# Quad_FC_V10_1.net
KiCad netlist of a schematic drawn in Altium Designer
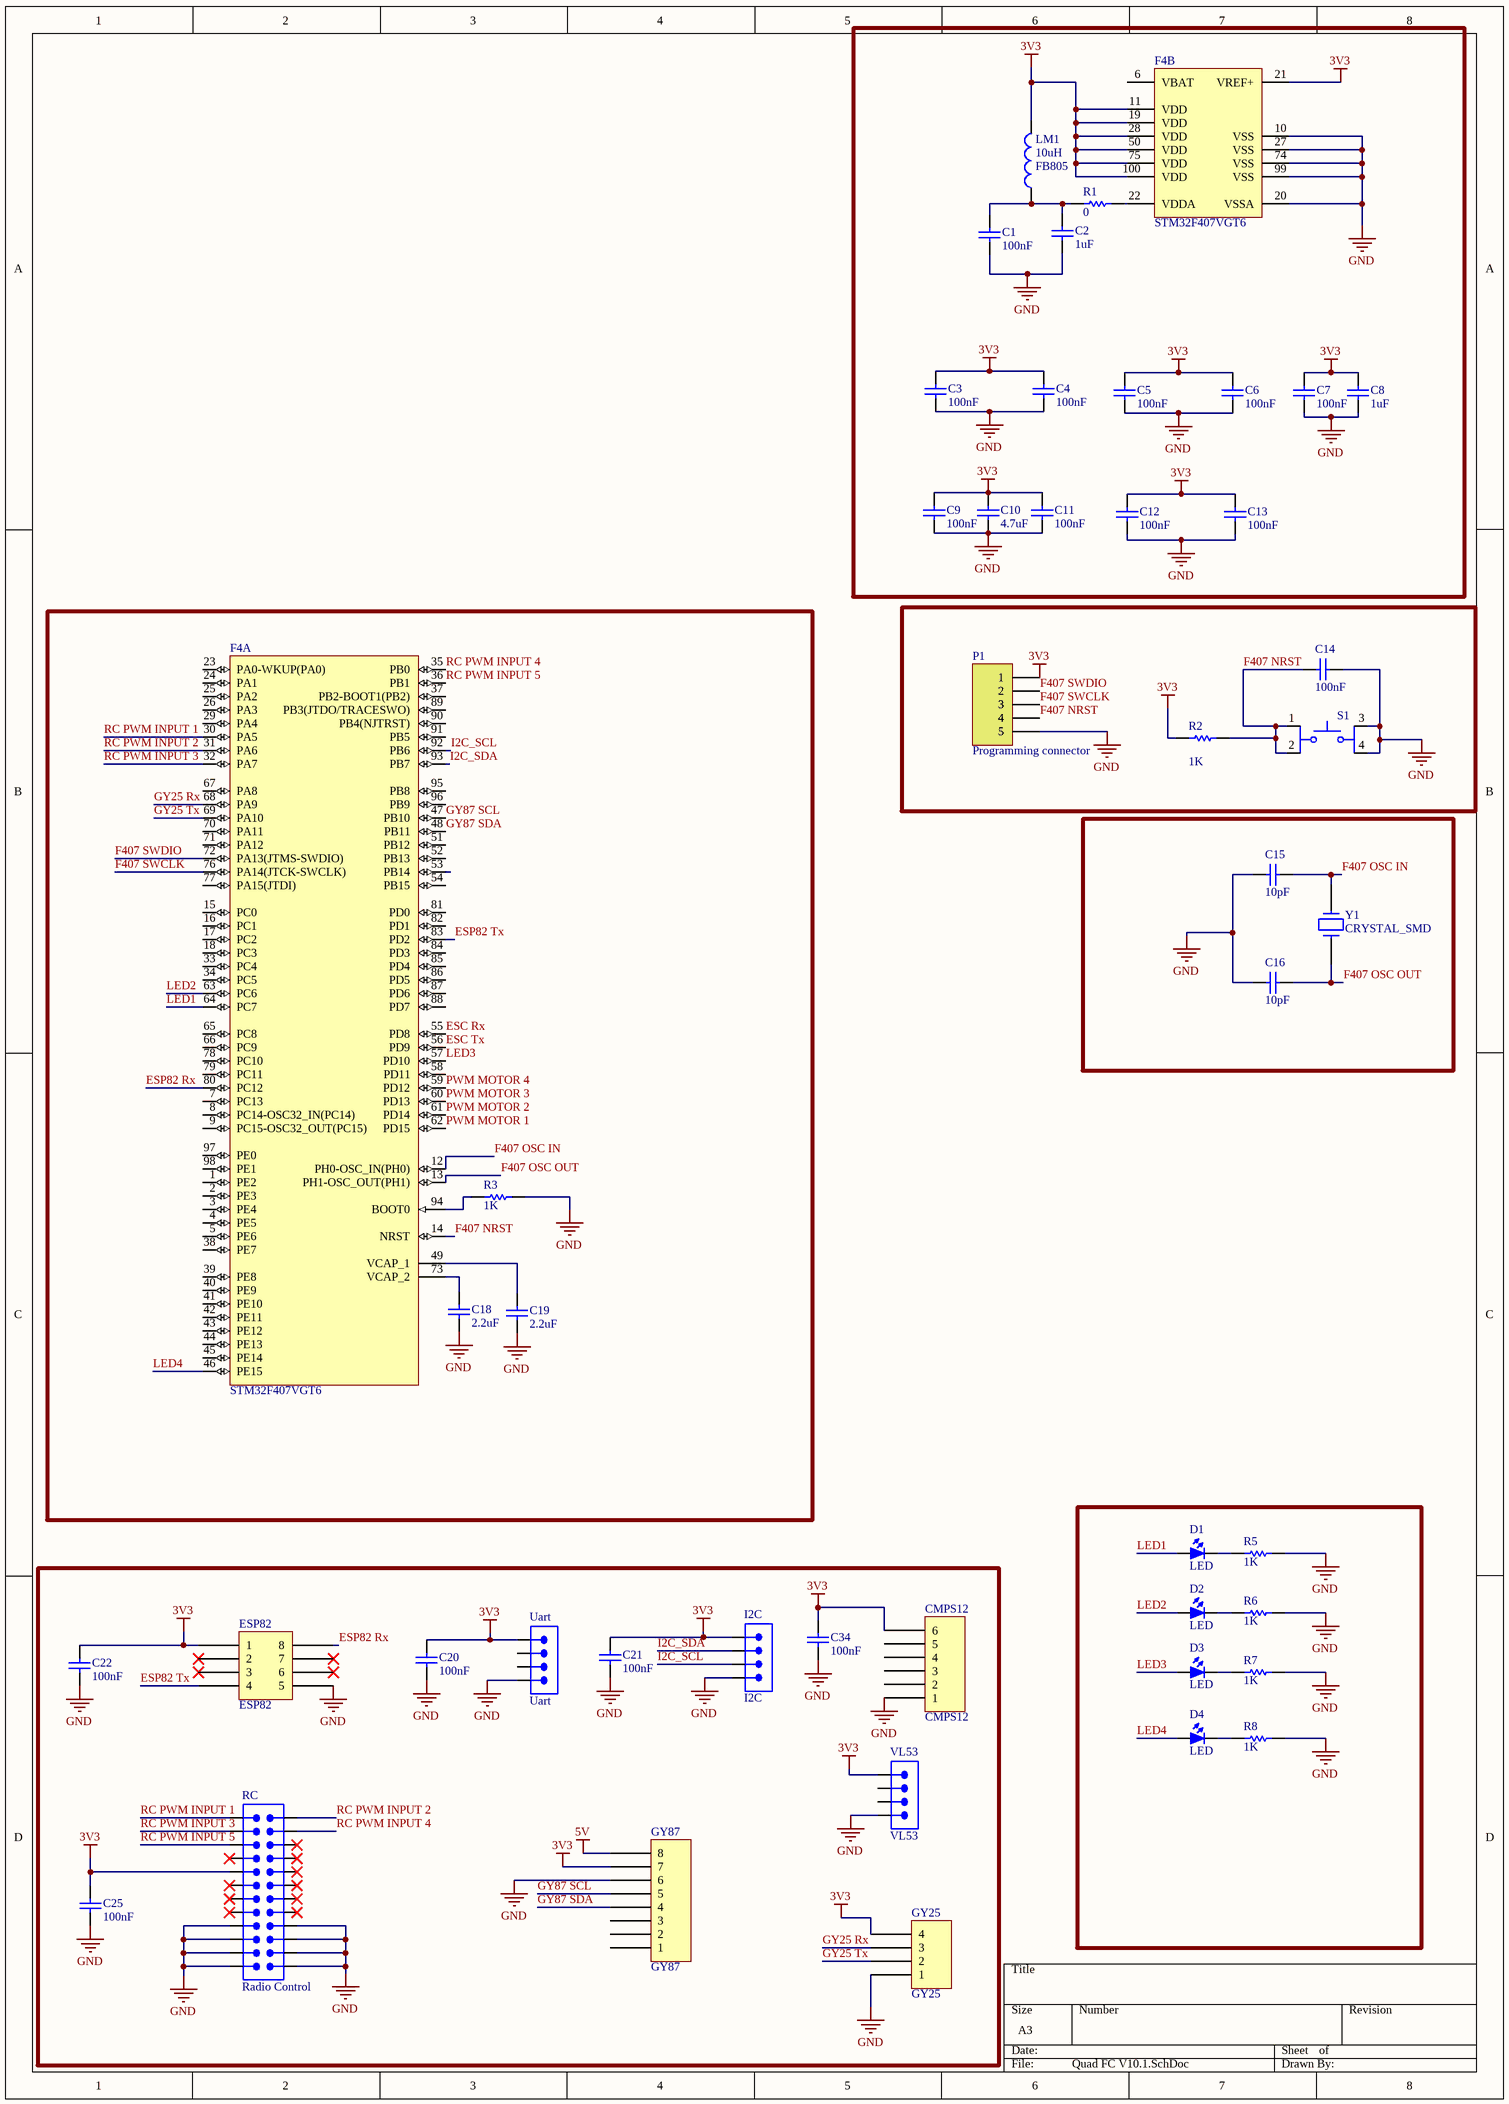
[diagram p0: Quad FC V10.1.SchDoc]

(export (version "E")
  (design (tool "Eeschema 10.0.6"))
  (components
    (comp (ref "C1")
      (value "100nF")
      (footprint "CAP0603")
      (description "F407VET6 Power CAP")
      (fields (field (name "DESIGNER") "Abbas Basereh"))
      (libsource (lib "2017AbbasBasereh9365731239 -ver1") (part "CAP SMD PACKAGE"))
    )
    (comp (ref "C2")
      (value "1uF")
      (footprint "CAP0603")
      (description "F407VET6 Power CAP")
      (fields (field (name "DESIGNER") "Abbas Basereh"))
      (libsource (lib "2017AbbasBasereh9365731239 -ver1") (part "CAP SMD PACKAGE"))
    )
    (comp (ref "C3")
      (value "100nF")
      (footprint "CAP0603")
      (description "F407VET6 Power CAP")
      (fields (field (name "DESIGNER") "Abbas Basereh"))
      (libsource (lib "2017AbbasBasereh9365731239 -ver1") (part "CAP SMD PACKAGE"))
    )
    (comp (ref "C4")
      (value "100nF")
      (footprint "CAP0603")
      (description "F407VET6 Power CAP")
      (fields (field (name "DESIGNER") "Abbas Basereh"))
      (libsource (lib "2017AbbasBasereh9365731239 -ver1") (part "CAP SMD PACKAGE"))
    )
    (comp (ref "C5")
      (value "100nF")
      (footprint "CAP0603")
      (description "F407VET6 Power CAP")
      (fields (field (name "DESIGNER") "Abbas Basereh"))
      (libsource (lib "2017AbbasBasereh9365731239 -ver1") (part "CAP SMD PACKAGE"))
    )
    (comp (ref "C6")
      (value "100nF")
      (footprint "CAP0603")
      (description "F407VET6 Power CAP")
      (fields (field (name "DESIGNER") "Abbas Basereh"))
      (libsource (lib "2017AbbasBasereh9365731239 -ver1") (part "CAP SMD PACKAGE"))
    )
    (comp (ref "C7")
      (value "100nF")
      (footprint "CAP0603")
      (description "F407VET6 Power CAP")
      (fields (field (name "DESIGNER") "Abbas Basereh"))
      (libsource (lib "2017AbbasBasereh9365731239 -ver1") (part "CAP SMD PACKAGE"))
    )
    (comp (ref "C8")
      (value "1uF")
      (footprint "CAP0603")
      (description "F407VET6 Power CAP")
      (fields (field (name "DESIGNER") "Abbas Basereh"))
      (libsource (lib "2017AbbasBasereh9365731239 -ver1") (part "CAP SMD PACKAGE"))
    )
    (comp (ref "C9")
      (value "100nF")
      (footprint "CAP0603")
      (description "F407VET6 Power CAP")
      (fields (field (name "DESIGNER") "Abbas Basereh"))
      (libsource (lib "2017AbbasBasereh9365731239 -ver1") (part "CAP SMD PACKAGE"))
    )
    (comp (ref "C10")
      (value "4.7uF")
      (footprint "CAP0603")
      (description "F407VET6 Power CAP")
      (fields (field (name "DESIGNER") "Abbas Basereh"))
      (libsource (lib "2017AbbasBasereh9365731239 -ver1") (part "CAP SMD PACKAGE"))
    )
    (comp (ref "C11")
      (value "100nF")
      (footprint "CAP0603")
      (description "F407VET6 Power CAP")
      (fields (field (name "DESIGNER") "Abbas Basereh"))
      (libsource (lib "2017AbbasBasereh9365731239 -ver1") (part "CAP SMD PACKAGE"))
    )
    (comp (ref "C12")
      (value "100nF")
      (footprint "CAP0603")
      (description "F407VET6 Power CAP")
      (fields (field (name "DESIGNER") "Abbas Basereh"))
      (libsource (lib "2017AbbasBasereh9365731239 -ver1") (part "CAP SMD PACKAGE"))
    )
    (comp (ref "C13")
      (value "100nF")
      (footprint "CAP0603")
      (description "F407VET6 Power CAP")
      (fields (field (name "DESIGNER") "Abbas Basereh"))
      (libsource (lib "2017AbbasBasereh9365731239 -ver1") (part "CAP SMD PACKAGE"))
    )
    (comp (ref "C14")
      (value "100nF")
      (footprint "CAP0603")
      (description "F407VET6 Power CAP")
      (fields (field (name "DESIGNER") "Abbas Basereh"))
      (libsource (lib "2017AbbasBasereh9365731239 -ver1") (part "CAP SMD PACKAGE"))
    )
    (comp (ref "C15")
      (value "10pF")
      (footprint "CAP0603")
      (description "F407VET6 Power CAP")
      (fields (field (name "DESIGNER") "Abbas Basereh"))
      (libsource (lib "2017AbbasBasereh9365731239 -ver1") (part "CAP SMD PACKAGE"))
    )
    (comp (ref "C16")
      (value "10pF")
      (footprint "CAP0603")
      (description "F407VET6 Power CAP")
      (fields (field (name "DESIGNER") "Abbas Basereh"))
      (libsource (lib "2017AbbasBasereh9365731239 -ver1") (part "CAP SMD PACKAGE"))
    )
    (comp (ref "C18")
      (value "2.2uF")
      (footprint "CAP0603")
      (description "F407VET6 Power CAP")
      (fields (field (name "DESIGNER") "Abbas Basereh"))
      (libsource (lib "2017AbbasBasereh9365731239 -ver1") (part "CAP SMD PACKAGE"))
    )
    (comp (ref "C19")
      (value "2.2uF")
      (footprint "CAP0603")
      (description "F407VET6 Power CAP")
      (fields (field (name "DESIGNER") "Abbas Basereh"))
      (libsource (lib "2017AbbasBasereh9365731239 -ver1") (part "CAP SMD PACKAGE"))
    )
    (comp (ref "C20")
      (value "100nF")
      (footprint "CAP0603")
      (description "F407VET6 Power CAP")
      (fields (field (name "DESIGNER") "Abbas Basereh"))
      (libsource (lib "2017AbbasBasereh9365731239 -ver1") (part "CAP SMD PACKAGE"))
    )
    (comp (ref "C21")
      (value "100nF")
      (footprint "CAP0603")
      (description "F407VET6 Power CAP")
      (fields (field (name "DESIGNER") "Abbas Basereh"))
      (libsource (lib "2017AbbasBasereh9365731239 -ver1") (part "CAP SMD PACKAGE"))
    )
    (comp (ref "C22")
      (value "100nF")
      (footprint "CAP0603")
      (description "F407VET6 Power CAP")
      (fields (field (name "DESIGNER") "Abbas Basereh"))
      (libsource (lib "2017AbbasBasereh9365731239 -ver1") (part "CAP SMD PACKAGE"))
    )
    (comp (ref "C25")
      (value "100nF")
      (footprint "CAP0603")
      (description "F407VET6 Power CAP")
      (fields (field (name "DESIGNER") "Abbas Basereh"))
      (libsource (lib "2017AbbasBasereh9365731239 -ver1") (part "CAP SMD PACKAGE"))
    )
    (comp (ref "C34")
      (value "100nF")
      (footprint "CAP0603")
      (description "F407VET6 Power CAP")
      (fields (field (name "DESIGNER") "Abbas Basereh"))
      (libsource (lib "2017AbbasBasereh9365731239 -ver1") (part "CAP SMD PACKAGE"))
    )
    (comp (ref "CMPS12")
      (value "CMPS12")
      (footprint "SAMTEC SSW-106-03-T-S")
      (description "CONN RCPT 6POS 0.1 TIN PCB")
      (fields (field (name "PART NUMBER") "SSW-106-03-T-S") (field (name "MANUFACTURER") "Samtec Inc."))
      (libsource (lib "Celestial Altium Library - altium_library (1)") (part "6 Pin"))
    )
    (comp (ref "D1")
      (value "LED")
      (footprint "0603 - LED")
      (description "Led")
      (fields (field (name "PUBLISHER") "Altium Limited"))
      (libsource (lib "Sajad_Altium_Library") (part "LED"))
    )
    (comp (ref "D2")
      (value "LED")
      (footprint "0603 - LED")
      (description "Led")
      (fields (field (name "PUBLISHER") "Altium Limited"))
      (libsource (lib "Sajad_Altium_Library") (part "LED"))
    )
    (comp (ref "D3")
      (value "LED")
      (footprint "0603 - LED")
      (description "Led")
      (fields (field (name "PUBLISHER") "Altium Limited"))
      (libsource (lib "Sajad_Altium_Library") (part "LED"))
    )
    (comp (ref "D4")
      (value "LED")
      (footprint "0603 - LED")
      (description "Led")
      (fields (field (name "PUBLISHER") "Altium Limited"))
      (libsource (lib "Sajad_Altium_Library") (part "LED"))
    )
    (comp (ref "ESP82")
      (value "ESP82")
      (footprint "HARWIN M20-7830445")
      (description "CONN RCPT 8POS 0.1 GOLD PCB")
      (fields (field (name "PART NUMBER") "M20-7830442") (field (name "MANUFACTURER") "Harwin Inc."))
      (libsource (lib "Celestial Altium Library - altium_library (1)") (part "2X4 PIN DU"))
    )
    (comp (ref "F4")
      (value "STM32F407VGT6")
      (footprint "STM-LQFP100_N")
      (fields (field (name "MANUFACTURER") "STMicroelectronics"))
      (libsource (lib "STMicroelectronics STM32 F4") (part "STM32F407VGT6"))
    )
    (comp (ref "GY25")
      (value "GY25")
      (footprint "SAMTEC SSW-104-03-T-S")
      (description "CONN RCPT 4POS 0.1 TIN PCB")
      (fields (field (name "PART NUMBER") "SSW-104-03-T-S") (field (name "MANUFACTURER") "Samtec Inc."))
      (libsource (lib "Celestial Altium Library - altium_library (1)") (part "4 Pin"))
    )
    (comp (ref "GY87")
      (value "GY87")
      (footprint "SAMTEC SSW-108-03-T-S")
      (description "CONN RCPT 8POS 0.1 TIN PCB")
      (fields (field (name "PART NUMBER") "SSW-108-03-T-S") (field (name "MANUFACTURER") "Samtec Inc."))
      (libsource (lib "Celestial Altium Library - altium_library (1)") (part "8 Pin"))
    )
    (comp (ref "I2C")
      (value "I2C")
      (footprint "JST BM04B-SURS-TF")
      (description "Male Header 1X04")
      (libsource (lib "SJ Sockets & Connectors") (part "MHDR_1X04"))
    )
    (comp (ref "LM1")
      (value "10uH")
      (footprint "0805L")
      (description "Inductor")
      (fields (field (name "ALTIUM_VALUE") "FB805") (field (name "PUBLISHER") "Altium Limited"))
      (libsource (lib "2017AbbasBasereh9365731239 -ver1") (part "L SMA 0.25W"))
    )
    (comp (ref "P1")
      (value "Programming connector")
      (footprint "Connector1X5")
      (description "Connector, 5-Pin2.5mm")
      (fields (field (name "PUBLISHER") "Altium Limited"))
      (libsource (lib "Sajad_Altium_Library") (part "Connector1x5"))
    )
    (comp (ref "R1")
      (value "0")
      (footprint "RES0603")
      (description "TOTAL SMD RESISTOR PACK")
      (fields (field (name "DESIGNER") "Abbas Basereh"))
      (libsource (lib "2017AbbasBasereh9365731239 -ver1") (part "RES SMD PACKAGE"))
    )
    (comp (ref "R2")
      (value "1K")
      (footprint "RES0603")
      (description "TOTAL SMD RESISTOR PACK")
      (fields (field (name "DESIGNER") "Abbas Basereh"))
      (libsource (lib "2017AbbasBasereh9365731239 -ver1") (part "RES SMD PACKAGE"))
    )
    (comp (ref "R3")
      (value "1K")
      (footprint "RES0603")
      (description "TOTAL SMD RESISTOR PACK")
      (fields (field (name "DESIGNER") "Abbas Basereh"))
      (libsource (lib "2017AbbasBasereh9365731239 -ver1") (part "RES SMD PACKAGE"))
    )
    (comp (ref "R5")
      (value "1K")
      (footprint "RES0603")
      (description "TOTAL SMD RESISTOR PACK")
      (fields (field (name "DESIGNER") "Abbas Basereh"))
      (libsource (lib "2017AbbasBasereh9365731239 -ver1") (part "RES SMD PACKAGE"))
    )
    (comp (ref "R6")
      (value "1K")
      (footprint "RES0603")
      (description "TOTAL SMD RESISTOR PACK")
      (fields (field (name "DESIGNER") "Abbas Basereh"))
      (libsource (lib "2017AbbasBasereh9365731239 -ver1") (part "RES SMD PACKAGE"))
    )
    (comp (ref "R7")
      (value "1K")
      (footprint "RES0603")
      (description "TOTAL SMD RESISTOR PACK")
      (fields (field (name "DESIGNER") "Abbas Basereh"))
      (libsource (lib "2017AbbasBasereh9365731239 -ver1") (part "RES SMD PACKAGE"))
    )
    (comp (ref "R8")
      (value "1K")
      (footprint "RES0603")
      (description "TOTAL SMD RESISTOR PACK")
      (fields (field (name "DESIGNER") "Abbas Basereh"))
      (libsource (lib "2017AbbasBasereh9365731239 -ver1") (part "RES SMD PACKAGE"))
    )
    (comp (ref "RC")
      (value "Radio Control")
      (footprint "HEADER8X3:HEADER8X3")
      (description "Male Header 2X12")
      (libsource (lib "SJ Sockets & Connectors") (part "MHDR_2X12"))
    )
    (comp (ref "S1")
      (value "~")
      (footprint "SW_TL3301FF160QG")
      (description "Tactile switch for manual RESET")
      (fields (field (name "MF") "E-Switch") (field (name "MP") "TL3301FF160QG"))
      (libsource (lib "Tactile switch 6x6") (part "TL3301FF160QG"))
    )
    (comp (ref "Uart")
      (value "Uart")
      (footprint "JST BM04B-SURS-TF")
      (description "Male Header 1X04")
      (libsource (lib "SJ Sockets & Connectors") (part "MHDR_1X04"))
    )
    (comp (ref "VL53")
      (value "VL53")
      (footprint "JST BM04B-SURS-TF")
      (description "Male Header 1X04")
      (libsource (lib "SJ Sockets & Connectors") (part "MHDR_1X04"))
    )
    (comp (ref "Y1")
      (value "CRYSTAL_SMD")
      (footprint "My_Crystal - SMD")
      (description "Crystal")
      (libsource (lib "AMINLIB") (part "CRYSTAL_SMD"))
    )
  )
  (nets
    (net (code "1") (name "/ESC Rx") (class "Default")
      (node (ref "F4") (pin "55") (pinfunction "PD8_55") (pintype "bidirectional"))
    )
    (net (code "2") (name "/ESC Tx") (class "Default")
      (node (ref "F4") (pin "56") (pinfunction "PD9_56") (pintype "bidirectional"))
    )
    (net (code "3") (name "/ESP82 Rx") (class "Default")
      (node (ref "ESP82") (pin "8") (pinfunction "8_8") (pintype "passive"))
      (node (ref "F4") (pin "80") (pinfunction "PC12_80") (pintype "bidirectional"))
    )
    (net (code "4") (name "/ESP82 Tx") (class "Default")
      (node (ref "ESP82") (pin "4") (pinfunction "4_4") (pintype "passive"))
      (node (ref "F4") (pin "83") (pinfunction "PD2_83") (pintype "bidirectional"))
    )
    (net (code "5") (name "/F407 NRST") (class "Default")
      (node (ref "C14") (pin "1") (pinfunction "1_1") (pintype "passive"))
      (node (ref "F4") (pin "14") (pinfunction "NRST_14") (pintype "bidirectional"))
      (node (ref "P1") (pin "4") (pinfunction "4_4") (pintype "passive"))
      (node (ref "R2") (pin "2") (pinfunction "2_2") (pintype "passive"))
      (node (ref "S1") (pin "1") (pinfunction "1_1") (pintype "passive"))
      (node (ref "S1") (pin "2") (pinfunction "2_2") (pintype "passive"))
    )
    (net (code "6") (name "/F407 OSC IN") (class "Default")
      (node (ref "C15") (pin "2") (pinfunction "2_2") (pintype "passive"))
      (node (ref "F4") (pin "12") (pinfunction "PH0-OSC_IN(PH0)_12") (pintype "bidirectional"))
      (node (ref "Y1") (pin "2") (pinfunction "2_2") (pintype "passive"))
    )
    (net (code "7") (name "/F407 OSC OUT") (class "Default")
      (node (ref "C16") (pin "1") (pinfunction "1_1") (pintype "passive"))
      (node (ref "F4") (pin "13") (pinfunction "PH1-OSC_OUT(PH1)_13") (pintype "bidirectional"))
      (node (ref "Y1") (pin "1") (pinfunction "1_1") (pintype "passive"))
    )
    (net (code "8") (name "/F407 SWCLK") (class "Default")
      (node (ref "F4") (pin "76") (pinfunction "PA14(JTCK-SWCLK)_76") (pintype "bidirectional"))
      (node (ref "P1") (pin "3") (pinfunction "3_3") (pintype "passive"))
    )
    (net (code "9") (name "/F407 SWDIO") (class "Default")
      (node (ref "F4") (pin "72") (pinfunction "PA13(JTMS-SWDIO)_72") (pintype "bidirectional"))
      (node (ref "P1") (pin "2") (pinfunction "2_2") (pintype "passive"))
    )
    (net (code "10") (name "/GY25 Rx") (class "Default")
      (node (ref "F4") (pin "68") (pinfunction "PA9_68") (pintype "bidirectional"))
      (node (ref "GY25") (pin "3") (pinfunction "3_3") (pintype "passive"))
    )
    (net (code "11") (name "/GY25 Tx") (class "Default")
      (node (ref "F4") (pin "69") (pinfunction "PA10_69") (pintype "bidirectional"))
      (node (ref "GY25") (pin "2") (pinfunction "2_2") (pintype "passive"))
    )
    (net (code "12") (name "/GY87 SCL") (class "Default")
      (node (ref "F4") (pin "47") (pinfunction "PB10_47") (pintype "bidirectional"))
      (node (ref "GY87") (pin "5") (pinfunction "5_5") (pintype "passive"))
    )
    (net (code "13") (name "/GY87 SDA") (class "Default")
      (node (ref "F4") (pin "48") (pinfunction "PB11_48") (pintype "bidirectional"))
      (node (ref "GY87") (pin "4") (pinfunction "4_4") (pintype "passive"))
    )
    (net (code "14") (name "/I2C_SCL") (class "Default")
      (node (ref "F4") (pin "92") (pinfunction "PB6_92") (pintype "bidirectional"))
      (node (ref "I2C") (pin "3") (pinfunction "3_3") (pintype "passive"))
    )
    (net (code "15") (name "/I2C_SDA") (class "Default")
      (node (ref "F4") (pin "93") (pinfunction "PB7_93") (pintype "bidirectional"))
      (node (ref "I2C") (pin "2") (pinfunction "2_2") (pintype "passive"))
    )
    (net (code "16") (name "/LED1") (class "Default")
      (node (ref "D1") (pin "1") (pinfunction "A_1") (pintype "passive"))
      (node (ref "F4") (pin "64") (pinfunction "PC7_64") (pintype "bidirectional"))
    )
    (net (code "17") (name "/LED2") (class "Default")
      (node (ref "D2") (pin "1") (pinfunction "A_1") (pintype "passive"))
      (node (ref "F4") (pin "63") (pinfunction "PC6_63") (pintype "bidirectional"))
    )
    (net (code "18") (name "/LED3") (class "Default")
      (node (ref "D3") (pin "1") (pinfunction "A_1") (pintype "passive"))
      (node (ref "F4") (pin "57") (pinfunction "PD10_57") (pintype "bidirectional"))
    )
    (net (code "19") (name "/LED4") (class "Default")
      (node (ref "D4") (pin "1") (pinfunction "A_1") (pintype "passive"))
      (node (ref "F4") (pin "46") (pinfunction "PE15_46") (pintype "bidirectional"))
    )
    (net (code "20") (name "/PWM MOTOR 1") (class "Default")
      (node (ref "F4") (pin "62") (pinfunction "PD15_62") (pintype "bidirectional"))
    )
    (net (code "21") (name "/PWM MOTOR 2") (class "Default")
      (node (ref "F4") (pin "61") (pinfunction "PD14_61") (pintype "bidirectional"))
    )
    (net (code "22") (name "/PWM MOTOR 3") (class "Default")
      (node (ref "F4") (pin "60") (pinfunction "PD13_60") (pintype "bidirectional"))
    )
    (net (code "23") (name "/PWM MOTOR 4") (class "Default")
      (node (ref "F4") (pin "59") (pinfunction "PD12_59") (pintype "bidirectional"))
    )
    (net (code "24") (name "/RC PWM INPUT 1") (class "Default")
      (node (ref "F4") (pin "30") (pinfunction "PA5_30") (pintype "bidirectional"))
      (node (ref "RC") (pin "1") (pinfunction "1_1") (pintype "passive"))
    )
    (net (code "25") (name "/RC PWM INPUT 2") (class "Default")
      (node (ref "F4") (pin "31") (pinfunction "PA6_31") (pintype "bidirectional"))
      (node (ref "RC") (pin "2") (pinfunction "2_2") (pintype "passive"))
    )
    (net (code "26") (name "/RC PWM INPUT 3") (class "Default")
      (node (ref "F4") (pin "32") (pinfunction "PA7_32") (pintype "bidirectional"))
      (node (ref "RC") (pin "3") (pinfunction "3_3") (pintype "passive"))
    )
    (net (code "27") (name "/RC PWM INPUT 4") (class "Default")
      (node (ref "F4") (pin "35") (pinfunction "PB0_35") (pintype "bidirectional"))
      (node (ref "RC") (pin "4") (pinfunction "4_4") (pintype "passive"))
    )
    (net (code "28") (name "/RC PWM INPUT 5") (class "Default")
      (node (ref "F4") (pin "36") (pinfunction "PB1_36") (pintype "bidirectional"))
      (node (ref "RC") (pin "5") (pinfunction "5_5") (pintype "passive"))
    )
    (net (code "29") (name "3V3") (class "Default")
      (node (ref "C10") (pin "2") (pinfunction "2_2") (pintype "passive"))
      (node (ref "C11") (pin "2") (pinfunction "2_2") (pintype "passive"))
      (node (ref "C12") (pin "2") (pinfunction "2_2") (pintype "passive"))
      (node (ref "C13") (pin "2") (pinfunction "2_2") (pintype "passive"))
      (node (ref "C20") (pin "1") (pinfunction "1_1") (pintype "passive"))
      (node (ref "C21") (pin "1") (pinfunction "1_1") (pintype "passive"))
      (node (ref "C22") (pin "1") (pinfunction "1_1") (pintype "passive"))
      (node (ref "C25") (pin "1") (pinfunction "1_1") (pintype "passive"))
      (node (ref "C3") (pin "2") (pinfunction "2_2") (pintype "passive"))
      (node (ref "C34") (pin "1") (pinfunction "1_1") (pintype "passive"))
      (node (ref "C4") (pin "2") (pinfunction "2_2") (pintype "passive"))
      (node (ref "C5") (pin "2") (pinfunction "2_2") (pintype "passive"))
      (node (ref "C6") (pin "2") (pinfunction "2_2") (pintype "passive"))
      (node (ref "C7") (pin "1") (pinfunction "1_1") (pintype "passive"))
      (node (ref "C8") (pin "1") (pinfunction "1_1") (pintype "passive"))
      (node (ref "C9") (pin "2") (pinfunction "2_2") (pintype "passive"))
      (node (ref "CMPS12") (pin "6") (pinfunction "6_6") (pintype "passive"))
      (node (ref "ESP82") (pin "1") (pinfunction "1_1") (pintype "passive"))
      (node (ref "F4") (pin "100") (pinfunction "VDD_100") (pintype "power_in"))
      (node (ref "F4") (pin "11") (pinfunction "VDD_11") (pintype "power_in"))
      (node (ref "F4") (pin "19") (pinfunction "VDD_19") (pintype "power_in"))
      (node (ref "F4") (pin "21") (pinfunction "VREF+_21") (pintype "power_in"))
      (node (ref "F4") (pin "28") (pinfunction "VDD_28") (pintype "power_in"))
      (node (ref "F4") (pin "50") (pinfunction "VDD_50") (pintype "power_in"))
      (node (ref "F4") (pin "75") (pinfunction "VDD_75") (pintype "power_in"))
      (node (ref "GY25") (pin "4") (pinfunction "4_4") (pintype "passive"))
      (node (ref "GY87") (pin "7") (pinfunction "7_7") (pintype "passive"))
      (node (ref "I2C") (pin "1") (pinfunction "1_1") (pintype "passive"))
      (node (ref "LM1") (pin "2") (pinfunction "2_2") (pintype "passive"))
      (node (ref "P1") (pin "1") (pinfunction "1_1") (pintype "passive"))
      (node (ref "R2") (pin "1") (pinfunction "1_1") (pintype "passive"))
      (node (ref "RC") (pin "9") (pinfunction "9_9") (pintype "passive"))
      (node (ref "Uart") (pin "1") (pinfunction "1_1") (pintype "passive"))
      (node (ref "VL53") (pin "1") (pinfunction "1_1") (pintype "passive"))
    )
    (net (code "30") (name "5V") (class "Default")
      (node (ref "GY87") (pin "8") (pinfunction "8_8") (pintype "passive"))
    )
    (net (code "31") (name "GND") (class "Default")
      (node (ref "C1") (pin "1") (pinfunction "1_1") (pintype "passive"))
      (node (ref "C10") (pin "1") (pinfunction "1_1") (pintype "passive"))
      (node (ref "C11") (pin "1") (pinfunction "1_1") (pintype "passive"))
      (node (ref "C12") (pin "1") (pinfunction "1_1") (pintype "passive"))
      (node (ref "C13") (pin "1") (pinfunction "1_1") (pintype "passive"))
      (node (ref "C14") (pin "2") (pinfunction "2_2") (pintype "passive"))
      (node (ref "C15") (pin "1") (pinfunction "1_1") (pintype "passive"))
      (node (ref "C16") (pin "2") (pinfunction "2_2") (pintype "passive"))
      (node (ref "C18") (pin "2") (pinfunction "2_2") (pintype "passive"))
      (node (ref "C19") (pin "2") (pinfunction "2_2") (pintype "passive"))
      (node (ref "C2") (pin "1") (pinfunction "1_1") (pintype "passive"))
      (node (ref "C20") (pin "2") (pinfunction "2_2") (pintype "passive"))
      (node (ref "C21") (pin "2") (pinfunction "2_2") (pintype "passive"))
      (node (ref "C22") (pin "2") (pinfunction "2_2") (pintype "passive"))
      (node (ref "C25") (pin "2") (pinfunction "2_2") (pintype "passive"))
      (node (ref "C3") (pin "1") (pinfunction "1_1") (pintype "passive"))
      (node (ref "C34") (pin "2") (pinfunction "2_2") (pintype "passive"))
      (node (ref "C4") (pin "1") (pinfunction "1_1") (pintype "passive"))
      (node (ref "C5") (pin "1") (pinfunction "1_1") (pintype "passive"))
      (node (ref "C6") (pin "1") (pinfunction "1_1") (pintype "passive"))
      (node (ref "C7") (pin "2") (pinfunction "2_2") (pintype "passive"))
      (node (ref "C8") (pin "2") (pinfunction "2_2") (pintype "passive"))
      (node (ref "C9") (pin "1") (pinfunction "1_1") (pintype "passive"))
      (node (ref "CMPS12") (pin "1") (pinfunction "1_1") (pintype "passive"))
      (node (ref "ESP82") (pin "5") (pinfunction "5_5") (pintype "passive"))
      (node (ref "F4") (pin "10") (pinfunction "VSS_10") (pintype "power_in"))
      (node (ref "F4") (pin "20") (pinfunction "VSSA_20") (pintype "power_in"))
      (node (ref "F4") (pin "27") (pinfunction "VSS_27") (pintype "power_in"))
      (node (ref "F4") (pin "74") (pinfunction "VSS_74") (pintype "power_in"))
      (node (ref "F4") (pin "99") (pinfunction "VSS_99") (pintype "power_in"))
      (node (ref "GY25") (pin "1") (pinfunction "1_1") (pintype "passive"))
      (node (ref "GY87") (pin "6") (pinfunction "6_6") (pintype "passive"))
      (node (ref "I2C") (pin "4") (pinfunction "4_4") (pintype "passive"))
      (node (ref "P1") (pin "5") (pinfunction "5_5") (pintype "passive"))
      (node (ref "R3") (pin "2") (pinfunction "2_2") (pintype "passive"))
      (node (ref "R5") (pin "2") (pinfunction "2_2") (pintype "passive"))
      (node (ref "R6") (pin "2") (pinfunction "2_2") (pintype "passive"))
      (node (ref "R7") (pin "2") (pinfunction "2_2") (pintype "passive"))
      (node (ref "R8") (pin "2") (pinfunction "2_2") (pintype "passive"))
      (node (ref "RC") (pin "17") (pinfunction "17_17") (pintype "passive"))
      (node (ref "RC") (pin "18") (pinfunction "18_18") (pintype "passive"))
      (node (ref "RC") (pin "19") (pinfunction "19_19") (pintype "passive"))
      (node (ref "RC") (pin "20") (pinfunction "20_20") (pintype "passive"))
      (node (ref "RC") (pin "21") (pinfunction "21_21") (pintype "passive"))
      (node (ref "RC") (pin "22") (pinfunction "22_22") (pintype "passive"))
      (node (ref "RC") (pin "23") (pinfunction "23_23") (pintype "passive"))
      (node (ref "RC") (pin "24") (pinfunction "24_24") (pintype "passive"))
      (node (ref "S1") (pin "3") (pinfunction "3_3") (pintype "passive"))
      (node (ref "S1") (pin "4") (pinfunction "4_4") (pintype "passive"))
      (node (ref "Uart") (pin "4") (pinfunction "4_4") (pintype "passive"))
      (node (ref "VL53") (pin "4") (pinfunction "4_4") (pintype "passive"))
    )
    (net (code "32") (name "Net-(C1-Pad2)") (class "Default")
      (node (ref "C1") (pin "2") (pinfunction "2_2") (pintype "passive"))
      (node (ref "C2") (pin "2") (pinfunction "2_2") (pintype "passive"))
      (node (ref "LM1") (pin "1") (pinfunction "1_1") (pintype "passive"))
      (node (ref "R1") (pin "1") (pinfunction "1_1") (pintype "passive"))
    )
    (net (code "33") (name "Net-(D1-K)") (class "Default")
      (node (ref "D1") (pin "2") (pinfunction "K_2") (pintype "passive"))
      (node (ref "R5") (pin "1") (pinfunction "1_1") (pintype "passive"))
    )
    (net (code "34") (name "Net-(D2-K)") (class "Default")
      (node (ref "D2") (pin "2") (pinfunction "K_2") (pintype "passive"))
      (node (ref "R6") (pin "1") (pinfunction "1_1") (pintype "passive"))
    )
    (net (code "35") (name "Net-(D3-K)") (class "Default")
      (node (ref "D3") (pin "2") (pinfunction "K_2") (pintype "passive"))
      (node (ref "R7") (pin "1") (pinfunction "1_1") (pintype "passive"))
    )
    (net (code "36") (name "Net-(D4-K)") (class "Default")
      (node (ref "D4") (pin "2") (pinfunction "K_2") (pintype "passive"))
      (node (ref "R8") (pin "1") (pinfunction "1_1") (pintype "passive"))
    )
    (net (code "37") (name "Net-(F4A-BOOT0)") (class "Default")
      (node (ref "F4") (pin "94") (pinfunction "BOOT0_94") (pintype "input"))
      (node (ref "R3") (pin "1") (pinfunction "1_1") (pintype "passive"))
    )
    (net (code "38") (name "Net-(F4A-VCAP_1)") (class "Default")
      (node (ref "C19") (pin "1") (pinfunction "1_1") (pintype "passive"))
      (node (ref "F4") (pin "49") (pinfunction "VCAP_1_49") (pintype "power_in"))
    )
    (net (code "39") (name "Net-(F4A-VCAP_2)") (class "Default")
      (node (ref "C18") (pin "1") (pinfunction "1_1") (pintype "passive"))
      (node (ref "F4") (pin "73") (pinfunction "VCAP_2_73") (pintype "power_in"))
    )
    (net (code "40") (name "Net-(F4B-VDDA)") (class "Default")
      (node (ref "F4") (pin "22") (pinfunction "VDDA_22") (pintype "power_in"))
      (node (ref "R1") (pin "2") (pinfunction "2_2") (pintype "passive"))
    )
    (net (code "41") (name "unconnected-(CMPS12-Pad2)") (class "Default")
      (node (ref "CMPS12") (pin "2") (pinfunction "2_2") (pintype "passive"))
    )
    (net (code "42") (name "unconnected-(CMPS12-Pad3)") (class "Default")
      (node (ref "CMPS12") (pin "3") (pinfunction "3_3") (pintype "passive"))
    )
    (net (code "43") (name "unconnected-(CMPS12-Pad4)") (class "Default")
      (node (ref "CMPS12") (pin "4") (pinfunction "4_4") (pintype "passive"))
    )
    (net (code "44") (name "unconnected-(CMPS12-Pad5)") (class "Default")
      (node (ref "CMPS12") (pin "5") (pinfunction "5_5") (pintype "passive"))
    )
    (net (code "45") (name "unconnected-(ESP82-Pad2)") (class "Default")
      (node (ref "ESP82") (pin "2") (pinfunction "2_2") (pintype "passive+no_connect"))
    )
    (net (code "46") (name "unconnected-(ESP82-Pad3)") (class "Default")
      (node (ref "ESP82") (pin "3") (pinfunction "3_3") (pintype "passive+no_connect"))
    )
    (net (code "47") (name "unconnected-(ESP82-Pad6)") (class "Default")
      (node (ref "ESP82") (pin "6") (pinfunction "6_6") (pintype "passive+no_connect"))
    )
    (net (code "48") (name "unconnected-(ESP82-Pad7)") (class "Default")
      (node (ref "ESP82") (pin "7") (pinfunction "7_7") (pintype "passive+no_connect"))
    )
    (net (code "49") (name "unconnected-(F4A-PA0-WKUP(PA0)-Pad23)") (class "Default")
      (node (ref "F4") (pin "23") (pinfunction "PA0-WKUP(PA0)_23") (pintype "bidirectional"))
    )
    (net (code "50") (name "unconnected-(F4A-PA1-Pad24)") (class "Default")
      (node (ref "F4") (pin "24") (pinfunction "PA1_24") (pintype "bidirectional"))
    )
    (net (code "51") (name "unconnected-(F4A-PA2-Pad25)") (class "Default")
      (node (ref "F4") (pin "25") (pinfunction "PA2_25") (pintype "bidirectional"))
    )
    (net (code "52") (name "unconnected-(F4A-PA3-Pad26)") (class "Default")
      (node (ref "F4") (pin "26") (pinfunction "PA3_26") (pintype "bidirectional"))
    )
    (net (code "53") (name "unconnected-(F4A-PA4-Pad29)") (class "Default")
      (node (ref "F4") (pin "29") (pinfunction "PA4_29") (pintype "bidirectional"))
    )
    (net (code "54") (name "unconnected-(F4A-PA8-Pad67)") (class "Default")
      (node (ref "F4") (pin "67") (pinfunction "PA8_67") (pintype "bidirectional"))
    )
    (net (code "55") (name "unconnected-(F4A-PA11-Pad70)") (class "Default")
      (node (ref "F4") (pin "70") (pinfunction "PA11_70") (pintype "bidirectional"))
    )
    (net (code "56") (name "unconnected-(F4A-PA12-Pad71)") (class "Default")
      (node (ref "F4") (pin "71") (pinfunction "PA12_71") (pintype "bidirectional"))
    )
    (net (code "57") (name "unconnected-(F4A-PA15(JTDI)-Pad77)") (class "Default")
      (node (ref "F4") (pin "77") (pinfunction "PA15(JTDI)_77") (pintype "bidirectional"))
    )
    (net (code "58") (name "unconnected-(F4A-PB2-BOOT1(PB2)-Pad37)") (class "Default")
      (node (ref "F4") (pin "37") (pinfunction "PB2-BOOT1(PB2)_37") (pintype "bidirectional"))
    )
    (net (code "59") (name "unconnected-(F4A-PB3(JTDO{slash}TRACESWO)-Pad89)") (class "Default")
      (node (ref "F4") (pin "89") (pinfunction "PB3(JTDO/TRACESWO)_89") (pintype "bidirectional"))
    )
    (net (code "60") (name "unconnected-(F4A-PB4(NJTRST)-Pad90)") (class "Default")
      (node (ref "F4") (pin "90") (pinfunction "PB4(NJTRST)_90") (pintype "bidirectional"))
    )
    (net (code "61") (name "unconnected-(F4A-PB5-Pad91)") (class "Default")
      (node (ref "F4") (pin "91") (pinfunction "PB5_91") (pintype "bidirectional"))
    )
    (net (code "62") (name "unconnected-(F4A-PB8-Pad95)") (class "Default")
      (node (ref "F4") (pin "95") (pinfunction "PB8_95") (pintype "bidirectional"))
    )
    (net (code "63") (name "unconnected-(F4A-PB9-Pad96)") (class "Default")
      (node (ref "F4") (pin "96") (pinfunction "PB9_96") (pintype "bidirectional"))
    )
    (net (code "64") (name "unconnected-(F4A-PB12-Pad51)") (class "Default")
      (node (ref "F4") (pin "51") (pinfunction "PB12_51") (pintype "bidirectional"))
    )
    (net (code "65") (name "unconnected-(F4A-PB13-Pad52)") (class "Default")
      (node (ref "F4") (pin "52") (pinfunction "PB13_52") (pintype "bidirectional"))
    )
    (net (code "66") (name "unconnected-(F4A-PB14-Pad53)") (class "Default")
      (node (ref "F4") (pin "53") (pinfunction "PB14_53") (pintype "bidirectional"))
    )
    (net (code "67") (name "unconnected-(F4A-PB15-Pad54)") (class "Default")
      (node (ref "F4") (pin "54") (pinfunction "PB15_54") (pintype "bidirectional"))
    )
    (net (code "68") (name "unconnected-(F4A-PC0-Pad15)") (class "Default")
      (node (ref "F4") (pin "15") (pinfunction "PC0_15") (pintype "bidirectional"))
    )
    (net (code "69") (name "unconnected-(F4A-PC1-Pad16)") (class "Default")
      (node (ref "F4") (pin "16") (pinfunction "PC1_16") (pintype "bidirectional"))
    )
    (net (code "70") (name "unconnected-(F4A-PC2-Pad17)") (class "Default")
      (node (ref "F4") (pin "17") (pinfunction "PC2_17") (pintype "bidirectional"))
    )
    (net (code "71") (name "unconnected-(F4A-PC3-Pad18)") (class "Default")
      (node (ref "F4") (pin "18") (pinfunction "PC3_18") (pintype "bidirectional"))
    )
    (net (code "72") (name "unconnected-(F4A-PC4-Pad33)") (class "Default")
      (node (ref "F4") (pin "33") (pinfunction "PC4_33") (pintype "bidirectional"))
    )
    (net (code "73") (name "unconnected-(F4A-PC5-Pad34)") (class "Default")
      (node (ref "F4") (pin "34") (pinfunction "PC5_34") (pintype "bidirectional"))
    )
    (net (code "74") (name "unconnected-(F4A-PC8-Pad65)") (class "Default")
      (node (ref "F4") (pin "65") (pinfunction "PC8_65") (pintype "bidirectional"))
    )
    (net (code "75") (name "unconnected-(F4A-PC9-Pad66)") (class "Default")
      (node (ref "F4") (pin "66") (pinfunction "PC9_66") (pintype "bidirectional"))
    )
    (net (code "76") (name "unconnected-(F4A-PC10-Pad78)") (class "Default")
      (node (ref "F4") (pin "78") (pinfunction "PC10_78") (pintype "bidirectional"))
    )
    (net (code "77") (name "unconnected-(F4A-PC11-Pad79)") (class "Default")
      (node (ref "F4") (pin "79") (pinfunction "PC11_79") (pintype "bidirectional"))
    )
    (net (code "78") (name "unconnected-(F4A-PC13-Pad7)") (class "Default")
      (node (ref "F4") (pin "7") (pinfunction "PC13_7") (pintype "bidirectional"))
    )
    (net (code "79") (name "unconnected-(F4A-PC14-OSC32_IN(PC14)-Pad8)") (class "Default")
      (node (ref "F4") (pin "8") (pinfunction "PC14-OSC32_IN(PC14)_8") (pintype "bidirectional"))
    )
    (net (code "80") (name "unconnected-(F4A-PC15-OSC32_OUT(PC15)-Pad9)") (class "Default")
      (node (ref "F4") (pin "9") (pinfunction "PC15-OSC32_OUT(PC15)_9") (pintype "bidirectional"))
    )
    (net (code "81") (name "unconnected-(F4A-PD0-Pad81)") (class "Default")
      (node (ref "F4") (pin "81") (pinfunction "PD0_81") (pintype "bidirectional"))
    )
    (net (code "82") (name "unconnected-(F4A-PD1-Pad82)") (class "Default")
      (node (ref "F4") (pin "82") (pinfunction "PD1_82") (pintype "bidirectional"))
    )
    (net (code "83") (name "unconnected-(F4A-PD3-Pad84)") (class "Default")
      (node (ref "F4") (pin "84") (pinfunction "PD3_84") (pintype "bidirectional"))
    )
    (net (code "84") (name "unconnected-(F4A-PD4-Pad85)") (class "Default")
      (node (ref "F4") (pin "85") (pinfunction "PD4_85") (pintype "bidirectional"))
    )
    (net (code "85") (name "unconnected-(F4A-PD5-Pad86)") (class "Default")
      (node (ref "F4") (pin "86") (pinfunction "PD5_86") (pintype "bidirectional"))
    )
    (net (code "86") (name "unconnected-(F4A-PD6-Pad87)") (class "Default")
      (node (ref "F4") (pin "87") (pinfunction "PD6_87") (pintype "bidirectional"))
    )
    (net (code "87") (name "unconnected-(F4A-PD7-Pad88)") (class "Default")
      (node (ref "F4") (pin "88") (pinfunction "PD7_88") (pintype "bidirectional"))
    )
    (net (code "88") (name "unconnected-(F4A-PD11-Pad58)") (class "Default")
      (node (ref "F4") (pin "58") (pinfunction "PD11_58") (pintype "bidirectional"))
    )
    (net (code "89") (name "unconnected-(F4A-PE0-Pad97)") (class "Default")
      (node (ref "F4") (pin "97") (pinfunction "PE0_97") (pintype "bidirectional"))
    )
    (net (code "90") (name "unconnected-(F4A-PE1-Pad98)") (class "Default")
      (node (ref "F4") (pin "98") (pinfunction "PE1_98") (pintype "bidirectional"))
    )
    (net (code "91") (name "unconnected-(F4A-PE2-Pad1)") (class "Default")
      (node (ref "F4") (pin "1") (pinfunction "PE2_1") (pintype "bidirectional"))
    )
    (net (code "92") (name "unconnected-(F4A-PE3-Pad2)") (class "Default")
      (node (ref "F4") (pin "2") (pinfunction "PE3_2") (pintype "bidirectional"))
    )
    (net (code "93") (name "unconnected-(F4A-PE4-Pad3)") (class "Default")
      (node (ref "F4") (pin "3") (pinfunction "PE4_3") (pintype "bidirectional"))
    )
    (net (code "94") (name "unconnected-(F4A-PE5-Pad4)") (class "Default")
      (node (ref "F4") (pin "4") (pinfunction "PE5_4") (pintype "bidirectional"))
    )
    (net (code "95") (name "unconnected-(F4A-PE6-Pad5)") (class "Default")
      (node (ref "F4") (pin "5") (pinfunction "PE6_5") (pintype "bidirectional"))
    )
    (net (code "96") (name "unconnected-(F4A-PE7-Pad38)") (class "Default")
      (node (ref "F4") (pin "38") (pinfunction "PE7_38") (pintype "bidirectional"))
    )
    (net (code "97") (name "unconnected-(F4A-PE8-Pad39)") (class "Default")
      (node (ref "F4") (pin "39") (pinfunction "PE8_39") (pintype "bidirectional"))
    )
    (net (code "98") (name "unconnected-(F4A-PE9-Pad40)") (class "Default")
      (node (ref "F4") (pin "40") (pinfunction "PE9_40") (pintype "bidirectional"))
    )
    (net (code "99") (name "unconnected-(F4A-PE10-Pad41)") (class "Default")
      (node (ref "F4") (pin "41") (pinfunction "PE10_41") (pintype "bidirectional"))
    )
    (net (code "100") (name "unconnected-(F4A-PE11-Pad42)") (class "Default")
      (node (ref "F4") (pin "42") (pinfunction "PE11_42") (pintype "bidirectional"))
    )
    (net (code "101") (name "unconnected-(F4A-PE12-Pad43)") (class "Default")
      (node (ref "F4") (pin "43") (pinfunction "PE12_43") (pintype "bidirectional"))
    )
    (net (code "102") (name "unconnected-(F4A-PE13-Pad44)") (class "Default")
      (node (ref "F4") (pin "44") (pinfunction "PE13_44") (pintype "bidirectional"))
    )
    (net (code "103") (name "unconnected-(F4A-PE14-Pad45)") (class "Default")
      (node (ref "F4") (pin "45") (pinfunction "PE14_45") (pintype "bidirectional"))
    )
    (net (code "104") (name "unconnected-(F4B-VBAT-Pad6)") (class "Default")
      (node (ref "F4") (pin "6") (pinfunction "VBAT_6") (pintype "power_in"))
    )
    (net (code "105") (name "unconnected-(GY87-Pad1)") (class "Default")
      (node (ref "GY87") (pin "1") (pinfunction "1_1") (pintype "passive"))
    )
    (net (code "106") (name "unconnected-(GY87-Pad2)") (class "Default")
      (node (ref "GY87") (pin "2") (pinfunction "2_2") (pintype "passive"))
    )
    (net (code "107") (name "unconnected-(GY87-Pad3)") (class "Default")
      (node (ref "GY87") (pin "3") (pinfunction "3_3") (pintype "passive"))
    )
    (net (code "108") (name "unconnected-(RC-Pad6)") (class "Default")
      (node (ref "RC") (pin "6") (pinfunction "6_6") (pintype "passive+no_connect"))
    )
    (net (code "109") (name "unconnected-(RC-Pad7)") (class "Default")
      (node (ref "RC") (pin "7") (pinfunction "7_7") (pintype "passive+no_connect"))
    )
    (net (code "110") (name "unconnected-(RC-Pad8)") (class "Default")
      (node (ref "RC") (pin "8") (pinfunction "8_8") (pintype "passive+no_connect"))
    )
    (net (code "111") (name "unconnected-(RC-Pad10)") (class "Default")
      (node (ref "RC") (pin "10") (pinfunction "10_10") (pintype "passive+no_connect"))
    )
    (net (code "112") (name "unconnected-(RC-Pad11)") (class "Default")
      (node (ref "RC") (pin "11") (pinfunction "11_11") (pintype "passive+no_connect"))
    )
    (net (code "113") (name "unconnected-(RC-Pad12)") (class "Default")
      (node (ref "RC") (pin "12") (pinfunction "12_12") (pintype "passive+no_connect"))
    )
    (net (code "114") (name "unconnected-(RC-Pad13)") (class "Default")
      (node (ref "RC") (pin "13") (pinfunction "13_13") (pintype "passive+no_connect"))
    )
    (net (code "115") (name "unconnected-(RC-Pad14)") (class "Default")
      (node (ref "RC") (pin "14") (pinfunction "14_14") (pintype "passive+no_connect"))
    )
    (net (code "116") (name "unconnected-(RC-Pad15)") (class "Default")
      (node (ref "RC") (pin "15") (pinfunction "15_15") (pintype "passive+no_connect"))
    )
    (net (code "117") (name "unconnected-(RC-Pad16)") (class "Default")
      (node (ref "RC") (pin "16") (pinfunction "16_16") (pintype "passive+no_connect"))
    )
    (net (code "118") (name "unconnected-(Uart-Pad2)") (class "Default")
      (node (ref "Uart") (pin "2") (pinfunction "2_2") (pintype "passive"))
    )
    (net (code "119") (name "unconnected-(Uart-Pad3)") (class "Default")
      (node (ref "Uart") (pin "3") (pinfunction "3_3") (pintype "passive"))
    )
    (net (code "120") (name "unconnected-(VL53-Pad2)") (class "Default")
      (node (ref "VL53") (pin "2") (pinfunction "2_2") (pintype "passive"))
    )
    (net (code "121") (name "unconnected-(VL53-Pad3)") (class "Default")
      (node (ref "VL53") (pin "3") (pinfunction "3_3") (pintype "passive"))
    )
  )
)
